# ltk-hall-main.net
KiCad netlist of a schematic drawn in Altium Designer
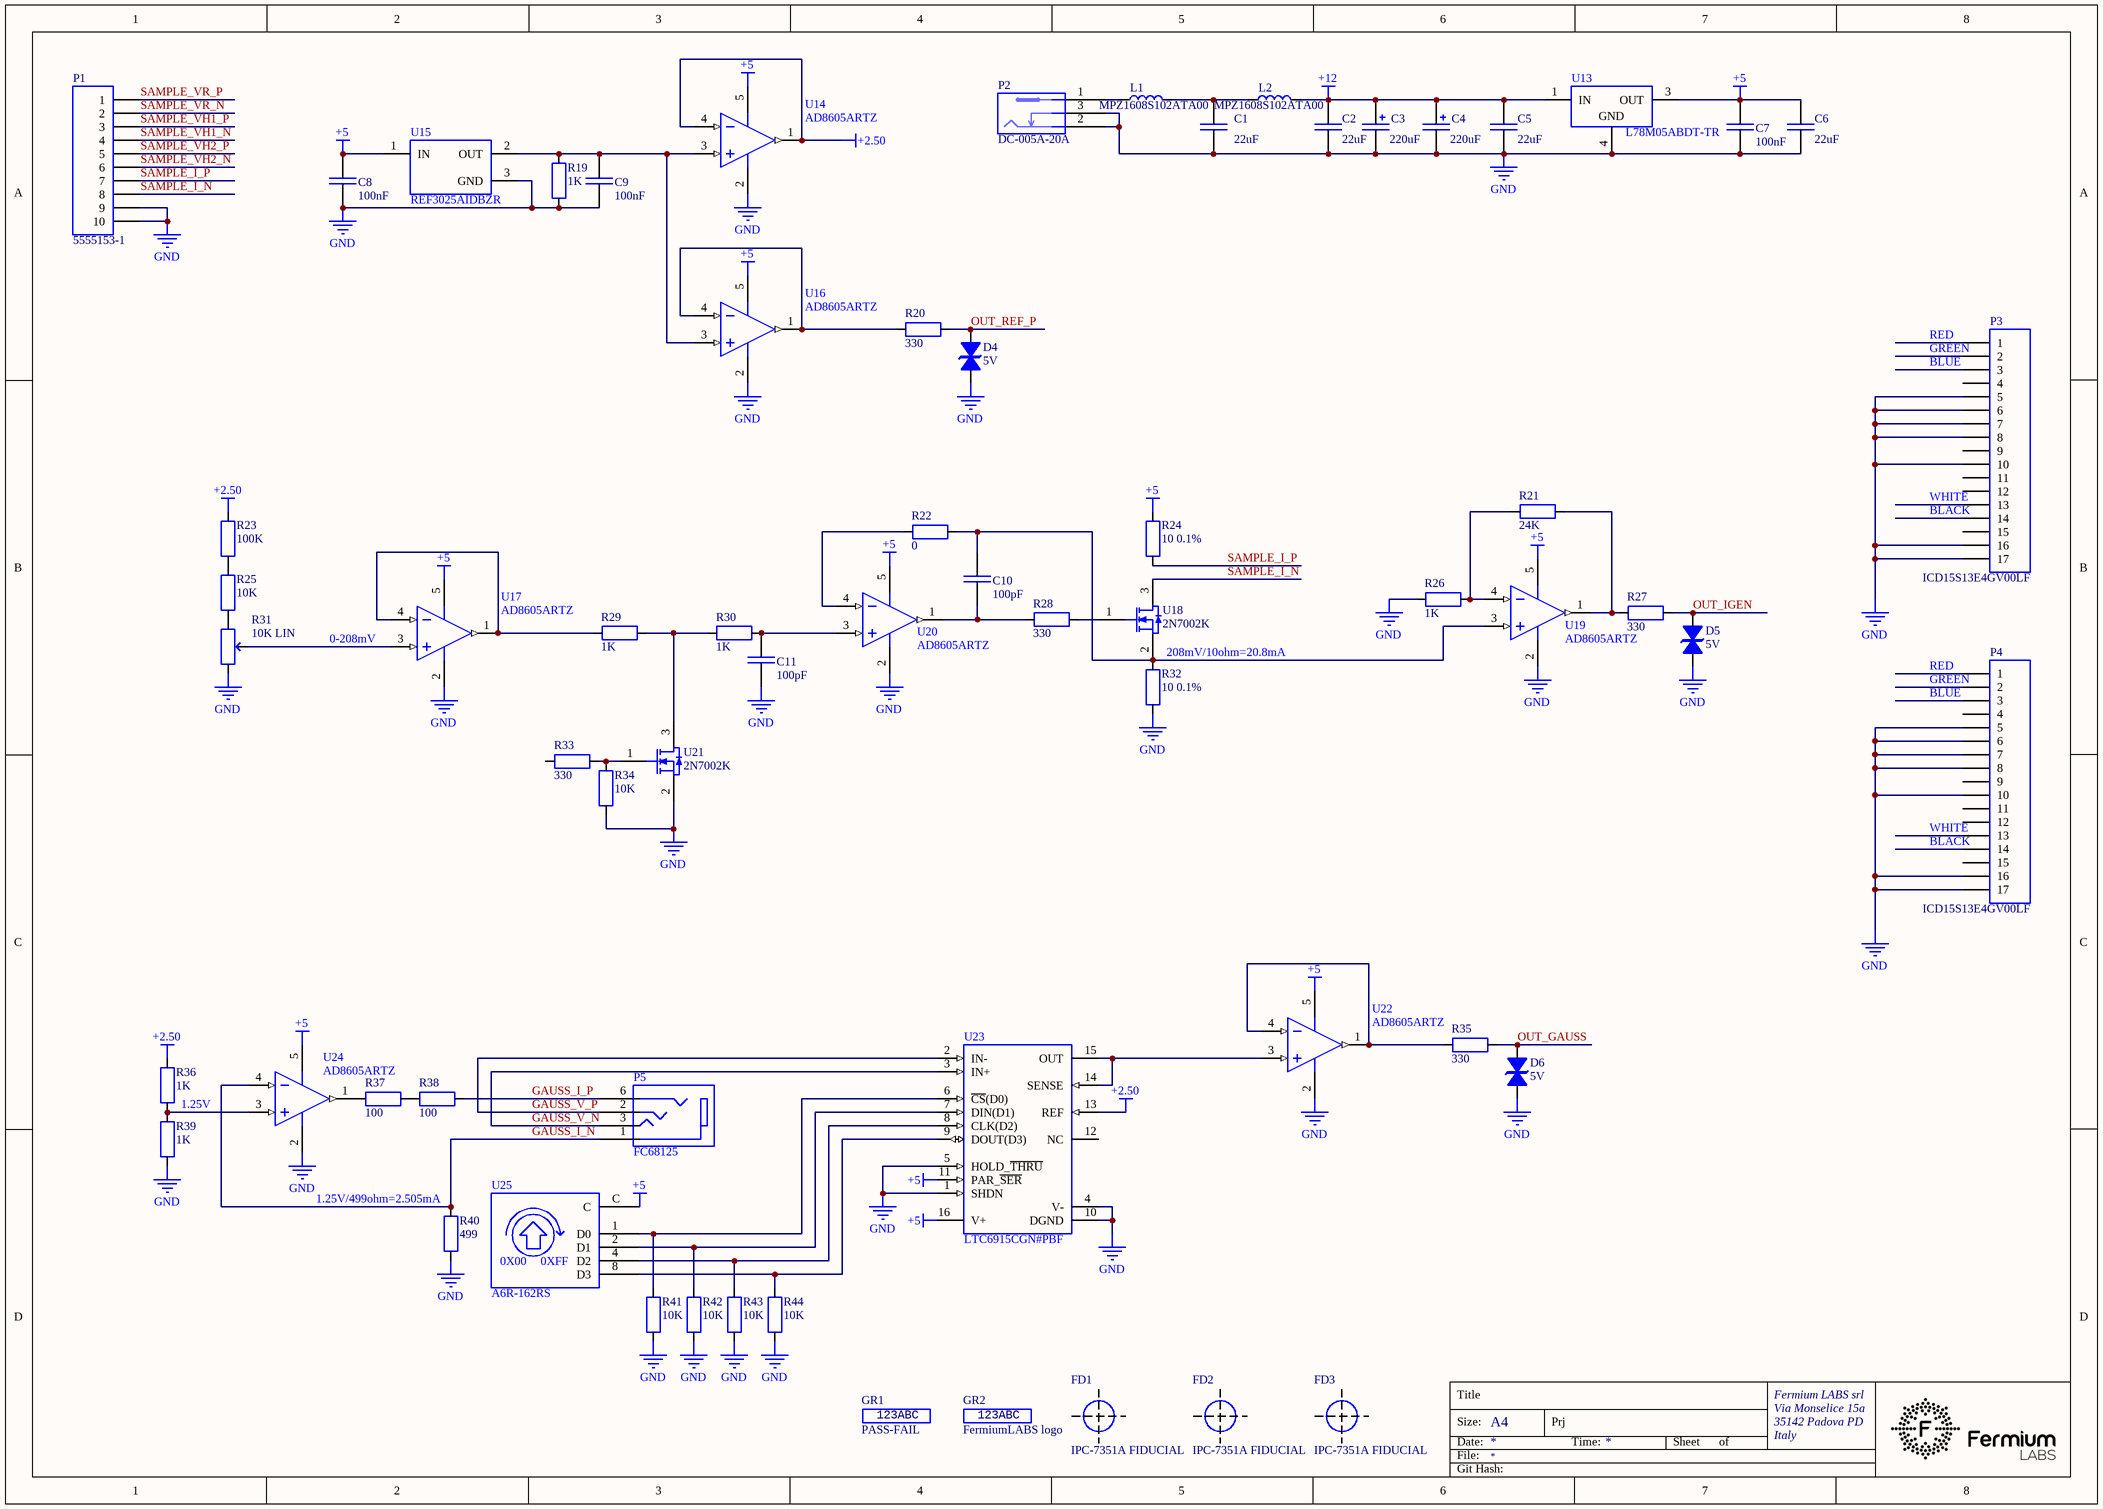
[diagram p0: ltk-hall-main.SchDoc]

(export (version "E")
  (design (tool "Eeschema 10.0.6"))
  (components
    (comp (ref "C1")
      (value "22uF")
      (footprint "CAP 0805_2012")
      (description "CAP SMD MLCC 22uF 25V 0805 X5R")
      (fields (field (name "PART NUMBER") "4e18e584-a077-4dfe-b9da-5e528e787323"))
      (libsource (lib "frmdblib") (part "GENERIC_C"))
    )
    (comp (ref "C2")
      (value "22uF")
      (footprint "CAP 0805_2012")
      (description "CAP SMD MLCC 22uF 25V 0805 X5R")
      (fields (field (name "PART NUMBER") "4e18e584-a077-4dfe-b9da-5e528e787323"))
      (libsource (lib "frmdblib") (part "GENERIC_C"))
    )
    (comp (ref "C3")
      (value "220uF")
      (footprint "3924B366-8672-45E9-B0BE-62DACC24E783")
      (description "CAP  THT ELEC 220uF 25V 20%")
      (fields (field (name "PART NUMBER") "1a28df19-6d3e-4a71-836c-f22920f8e8ab"))
      (libsource (lib "frmdblib") (part "GENERIC_C_ELEC"))
    )
    (comp (ref "C4")
      (value "220uF")
      (footprint "3924B366-8672-45E9-B0BE-62DACC24E783")
      (description "CAP  THT ELEC 220uF 25V 20%")
      (fields (field (name "PART NUMBER") "1a28df19-6d3e-4a71-836c-f22920f8e8ab"))
      (libsource (lib "frmdblib") (part "GENERIC_C_ELEC"))
    )
    (comp (ref "C5")
      (value "22uF")
      (footprint "CAP 0805_2012")
      (description "CAP SMD MLCC 22uF 25V 0805 X5R")
      (fields (field (name "PART NUMBER") "4e18e584-a077-4dfe-b9da-5e528e787323"))
      (libsource (lib "frmdblib") (part "GENERIC_C"))
    )
    (comp (ref "C6")
      (value "22uF")
      (footprint "CAP 0805_2012")
      (description "CAP SMD MLCC 22uF 25V 0805 X5R")
      (fields (field (name "PART NUMBER") "4e18e584-a077-4dfe-b9da-5e528e787323"))
      (libsource (lib "frmdblib") (part "GENERIC_C"))
    )
    (comp (ref "C7")
      (value "100nF")
      (footprint "CAP 0603_1608")
      (description "CAP SMD MLCC 100nF 25V 0603 X7R")
      (fields (field (name "PART NUMBER") "02841f84-ac15-41b5-9e17-915f8f067828"))
      (libsource (lib "frmdblib") (part "GENERIC_C"))
    )
    (comp (ref "C8")
      (value "100nF")
      (footprint "CAP 0603_1608")
      (description "CAP SMD MLCC 100nF 25V 0603 X7R")
      (fields (field (name "PART NUMBER") "02841f84-ac15-41b5-9e17-915f8f067828"))
      (libsource (lib "frmdblib") (part "GENERIC_C"))
    )
    (comp (ref "C9")
      (value "100nF")
      (footprint "CAP 0603_1608")
      (description "CAP SMD MLCC 100nF 25V 0603 X7R")
      (fields (field (name "PART NUMBER") "02841f84-ac15-41b5-9e17-915f8f067828"))
      (libsource (lib "frmdblib") (part "GENERIC_C"))
    )
    (comp (ref "C10")
      (value "100pF")
      (footprint "CAP 0603_1608")
      (description "CAP SMD MLCC 100pF 100V 0603 C0G/NP0")
      (fields (field (name "PART NUMBER") "ccf679fd-1b09-4431-be81-04c3ce295510"))
      (libsource (lib "frmdblib") (part "GENERIC_C"))
    )
    (comp (ref "C11")
      (value "100pF")
      (footprint "CAP 0603_1608")
      (description "CAP SMD MLCC 100pF 100V 0603 C0G/NP0")
      (fields (field (name "PART NUMBER") "ccf679fd-1b09-4431-be81-04c3ce295510"))
      (libsource (lib "frmdblib") (part "GENERIC_C"))
    )
    (comp (ref "D4")
      (value "5V")
      (footprint "SOD523F")
      (description "DIODE SMD TVS 5V BIDIRECTIONAL SOD-523")
      (fields (field (name "PART NUMBER") "daa58212-38e2-4326-a156-8e48058c46f1"))
      (libsource (lib "frmdblib") (part "GENERIC_D_TVS_BI"))
    )
    (comp (ref "D5")
      (value "5V")
      (footprint "SOD523F")
      (description "DIODE SMD TVS 5V BIDIRECTIONAL SOD-523")
      (fields (field (name "PART NUMBER") "daa58212-38e2-4326-a156-8e48058c46f1"))
      (libsource (lib "frmdblib") (part "GENERIC_D_TVS_BI"))
    )
    (comp (ref "D6")
      (value "5V")
      (footprint "SOD523F")
      (description "DIODE SMD TVS 5V BIDIRECTIONAL SOD-523")
      (fields (field (name "PART NUMBER") "daa58212-38e2-4326-a156-8e48058c46f1"))
      (libsource (lib "frmdblib") (part "GENERIC_D_TVS_BI"))
    )
    (comp (ref "FD1")
      (value "IPC-7351A FIDUCIAL")
      (footprint "FIDUCIAL-IPC-7351A")
      (description "GRAPHICS FIDUCIAL IPC-7351A")
      (fields (field (name "PART NUMBER") "19da4612-eb95-43bb-9984-553a52b2a224"))
      (libsource (lib "frmdblib") (part "GENERIC_FIDUCIAL"))
    )
    (comp (ref "FD2")
      (value "IPC-7351A FIDUCIAL")
      (footprint "FIDUCIAL-IPC-7351A")
      (description "GRAPHICS FIDUCIAL IPC-7351A")
      (fields (field (name "PART NUMBER") "19da4612-eb95-43bb-9984-553a52b2a224"))
      (libsource (lib "frmdblib") (part "GENERIC_FIDUCIAL"))
    )
    (comp (ref "FD3")
      (value "IPC-7351A FIDUCIAL")
      (footprint "FIDUCIAL-IPC-7351A")
      (description "GRAPHICS FIDUCIAL IPC-7351A")
      (fields (field (name "PART NUMBER") "19da4612-eb95-43bb-9984-553a52b2a224"))
      (libsource (lib "frmdblib") (part "GENERIC_FIDUCIAL"))
    )
    (comp (ref "GR1")
      (value "PASS-FAIL")
      (footprint "0B1556B7-A534-4801-B57D-01EFA34B1205")
      (description "GRAPHICS PASS-FAIL MARK")
      (fields (field (name "PART NUMBER") "d1abe19f-3fed-4f20-b2ed-afc0ffbc6628"))
      (libsource (lib "frmdblib") (part "GENERIC_GRAPHIC"))
    )
    (comp (ref "GR2")
      (value "FermiumLABS logo")
      (footprint "5394DE47-A0E8-4329-8464-7791B7C19310")
      (description "GRAPHICS LOGO FERMIUM LABS SRL")
      (fields (field (name "PART NUMBER") "50f8ea88-0034-49fe-a263-d8e97bc35e2f"))
      (libsource (lib "frmdblib") (part "GENERIC_GRAPHIC"))
    )
    (comp (ref "L1")
      (value "MPZ1608S102ATA00")
      (footprint "FER 0603_1608")
      (description "FER SMD CHIP 0603 800mA 1K@100MHz 300mOhm")
      (fields (field (name "PART NUMBER") "a4b2e015-bf25-47b8-954c-a5b040744a3a"))
      (libsource (lib "frmdblib") (part "GENERIC_L"))
    )
    (comp (ref "L2")
      (value "MPZ1608S102ATA00")
      (footprint "FER 0603_1608")
      (description "FER SMD CHIP 0603 800mA 1K@100MHz 300mOhm")
      (fields (field (name "PART NUMBER") "a4b2e015-bf25-47b8-954c-a5b040744a3a"))
      (libsource (lib "frmdblib") (part "GENERIC_L"))
    )
    (comp (ref "P1")
      (value "5555153-1")
      (footprint "03FA2727-72E9-446E-856D-3DD573B1EBDD")
      (description "CONN RJ45 SHIELDED")
      (fields (field (name "PART NUMBER") "f401b84a-9695-45b1-951e-00bef0039069"))
      (libsource (lib "frmdblib") (part "Header 10"))
    )
    (comp (ref "P2")
      (value "DC-005A-20A")
      (footprint "F0972D8A-C5C0-4A84-836D-A9666EE65C2D")
      (description "CONN THT DC JACK 0.5A 30VDC 5Kcycles")
      (fields (field (name "PART NUMBER") "b53db51a-1725-412b-9039-fa7a45c7c438"))
      (libsource (lib "frmdblib") (part "34A1CD0B-E262-46EF-B9F1-39CB809C308F"))
    )
    (comp (ref "P3")
      (value "ICD15S13E4GV00LF")
      (footprint "66D8AC91-DC10-42D3-BF25-693004815827")
      (description "CONN D-SUB HD 15POLES BLACK THT")
      (fields (field (name "PART NUMBER") "af155709-b835-40ac-b9b5-4a44b0fd2777"))
      (libsource (lib "frmdblib") (part "Header 17"))
    )
    (comp (ref "P4")
      (value "ICD15S13E4GV00LF")
      (footprint "66D8AC91-DC10-42D3-BF25-693004815827")
      (description "CONN D-SUB HD 15POLES BLACK THT")
      (fields (field (name "PART NUMBER") "af155709-b835-40ac-b9b5-4a44b0fd2777"))
      (libsource (lib "frmdblib") (part "Header 17"))
    )
    (comp (ref "P5")
      (value "FC68125")
      (footprint "977BFFC7-4CFC-4119-A8B4-AB88E5A1DB2B")
      (description "CONN JACK 3.5MM 4POLE THT")
      (fields (field (name "PART NUMBER") "3e3c57e9-f1b8-4c12-8bb1-97da9eb9c220"))
      (libsource (lib "frmdblib") (part "A6099F20-3616-40CA-8CCB-374681413BA7"))
    )
    (comp (ref "R19")
      (value "1K")
      (footprint "RES 0603_1608")
      (description "RES SMD 1K OHM 1% 1/10W 0603")
      (fields (field (name "PART NUMBER") "a678220f-9e9d-4863-a833-9993504f723c"))
      (libsource (lib "frmdblib") (part "GENERIC_R"))
    )
    (comp (ref "R20")
      (value "330")
      (description "RES SMD 330 OHM 1% 1/10W 0603")
      (fields (field (name "PART NUMBER") "e8555d7b-eeda-4727-b2e1-550cdc03d819"))
      (libsource (lib "frmdblib") (part "GENERIC_R"))
    )
    (comp (ref "R21")
      (value "24K")
      (description "RES SMD 24K OHM 1% 1/10W 0603")
      (fields (field (name "PART NUMBER") "89bb9559-07ab-4a9e-ba67-95cb66f30425"))
      (libsource (lib "frmdblib") (part "GENERIC_R"))
    )
    (comp (ref "R22")
      (value "0")
      (footprint "RES 0603_1608")
      (description "RES SMD 0 OHM 5% 1/10W 0603")
      (fields (field (name "PART NUMBER") "6ae227f9-847f-4766-8522-e11a83531204"))
      (libsource (lib "frmdblib") (part "GENERIC_R"))
    )
    (comp (ref "R23")
      (value "100K")
      (description "RES SMD 100K OHM 1% 1/16W 0402")
      (fields (field (name "PART NUMBER") "a6f23dcb-1502-42e9-827e-4bdfa60be22f"))
      (libsource (lib "frmdblib") (part "GENERIC_R"))
    )
    (comp (ref "R24")
      (value "10 0.1%")
      (footprint "RES 0603_1608")
      (description "RES SMD 10 OHM 0.1% 1/16W 25ppm  0603")
      (fields (field (name "PART NUMBER") "f0166db1-b7e4-4c18-9511-2907615c1c51"))
      (libsource (lib "frmdblib") (part "GENERIC_R"))
    )
    (comp (ref "R25")
      (value "10K")
      (footprint "RES 0603_1608")
      (description "RES SMD 10K OHM 1% 1/10W 0603")
      (fields (field (name "PART NUMBER") "93242766-ba1d-462d-b58f-ce1dfc4129c8"))
      (libsource (lib "frmdblib") (part "GENERIC_R"))
    )
    (comp (ref "R26")
      (value "1K")
      (footprint "RES 0603_1608")
      (description "RES SMD 1K OHM 1% 1/10W 0603")
      (fields (field (name "PART NUMBER") "a678220f-9e9d-4863-a833-9993504f723c"))
      (libsource (lib "frmdblib") (part "GENERIC_R"))
    )
    (comp (ref "R27")
      (value "330")
      (description "RES SMD 330 OHM 1% 1/10W 0603")
      (fields (field (name "PART NUMBER") "e8555d7b-eeda-4727-b2e1-550cdc03d819"))
      (libsource (lib "frmdblib") (part "GENERIC_R"))
    )
    (comp (ref "R28")
      (value "330")
      (description "RES SMD 330 OHM 1% 1/10W 0603")
      (fields (field (name "PART NUMBER") "e8555d7b-eeda-4727-b2e1-550cdc03d819"))
      (libsource (lib "frmdblib") (part "GENERIC_R"))
    )
    (comp (ref "R29")
      (value "1K")
      (footprint "RES 0603_1608")
      (description "RES SMD 1K OHM 1% 1/10W 0603")
      (fields (field (name "PART NUMBER") "a678220f-9e9d-4863-a833-9993504f723c"))
      (libsource (lib "frmdblib") (part "GENERIC_R"))
    )
    (comp (ref "R30")
      (value "1K")
      (footprint "RES 0603_1608")
      (description "RES SMD 1K OHM 1% 1/10W 0603")
      (fields (field (name "PART NUMBER") "a678220f-9e9d-4863-a833-9993504f723c"))
      (libsource (lib "frmdblib") (part "GENERIC_R"))
    )
    (comp (ref "R31")
      (value "10K LIN")
      (footprint "2EF88547-EDEF-4A49-A522-C215618D4BC7")
      (description "POT 10K 20% SHAFT 6mmx7.4mm LIN")
      (fields (field (name "PART NUMBER") "3df905ea-1e80-4add-859d-a36edd7f106c"))
      (libsource (lib "frmdblib") (part "GENERIC_R_VAR"))
    )
    (comp (ref "R32")
      (value "10 0.1%")
      (footprint "RES 0603_1608")
      (description "RES SMD 10 OHM 0.1% 1/16W 25ppm  0603")
      (fields (field (name "PART NUMBER") "f0166db1-b7e4-4c18-9511-2907615c1c51"))
      (libsource (lib "frmdblib") (part "GENERIC_R"))
    )
    (comp (ref "R33")
      (value "330")
      (description "RES SMD 330 OHM 1% 1/10W 0603")
      (fields (field (name "PART NUMBER") "e8555d7b-eeda-4727-b2e1-550cdc03d819"))
      (libsource (lib "frmdblib") (part "GENERIC_R"))
    )
    (comp (ref "R34")
      (value "10K")
      (footprint "RES 0603_1608")
      (description "RES SMD 10K OHM 1% 1/10W 0603")
      (fields (field (name "PART NUMBER") "93242766-ba1d-462d-b58f-ce1dfc4129c8"))
      (libsource (lib "frmdblib") (part "GENERIC_R"))
    )
    (comp (ref "R35")
      (value "330")
      (description "RES SMD 330 OHM 1% 1/10W 0603")
      (fields (field (name "PART NUMBER") "e8555d7b-eeda-4727-b2e1-550cdc03d819"))
      (libsource (lib "frmdblib") (part "GENERIC_R"))
    )
    (comp (ref "R36")
      (value "1K")
      (footprint "RES 0603_1608")
      (description "RES SMD 1K OHM 1% 1/10W 0603")
      (fields (field (name "PART NUMBER") "a678220f-9e9d-4863-a833-9993504f723c"))
      (libsource (lib "frmdblib") (part "GENERIC_R"))
    )
    (comp (ref "R37")
      (value "100")
      (description "RES SMD 100 OHM 1% 1/10W 0603")
      (fields (field (name "PART NUMBER") "0a6c4b74-f837-4563-b154-6e196d753525"))
      (libsource (lib "frmdblib") (part "GENERIC_R"))
    )
    (comp (ref "R38")
      (value "100")
      (description "RES SMD 100 OHM 1% 1/10W 0603")
      (fields (field (name "PART NUMBER") "0a6c4b74-f837-4563-b154-6e196d753525"))
      (libsource (lib "frmdblib") (part "GENERIC_R"))
    )
    (comp (ref "R39")
      (value "1K")
      (footprint "RES 0603_1608")
      (description "RES SMD 1K OHM 1% 1/10W 0603")
      (fields (field (name "PART NUMBER") "a678220f-9e9d-4863-a833-9993504f723c"))
      (libsource (lib "frmdblib") (part "GENERIC_R"))
    )
    (comp (ref "R40")
      (value "499")
      (description "RES SMD 499 OHM 1% 1/10W 0603")
      (fields (field (name "PART NUMBER") "3a10051a-dd65-4121-b0b9-1b40351a1843"))
      (libsource (lib "frmdblib") (part "GENERIC_R"))
    )
    (comp (ref "R41")
      (value "10K")
      (footprint "RES 0603_1608")
      (description "RES SMD 10K OHM 1% 1/10W 0603")
      (fields (field (name "PART NUMBER") "93242766-ba1d-462d-b58f-ce1dfc4129c8"))
      (libsource (lib "frmdblib") (part "GENERIC_R"))
    )
    (comp (ref "R42")
      (value "10K")
      (footprint "RES 0603_1608")
      (description "RES SMD 10K OHM 1% 1/10W 0603")
      (fields (field (name "PART NUMBER") "93242766-ba1d-462d-b58f-ce1dfc4129c8"))
      (libsource (lib "frmdblib") (part "GENERIC_R"))
    )
    (comp (ref "R43")
      (value "10K")
      (footprint "RES 0603_1608")
      (description "RES SMD 10K OHM 1% 1/10W 0603")
      (fields (field (name "PART NUMBER") "93242766-ba1d-462d-b58f-ce1dfc4129c8"))
      (libsource (lib "frmdblib") (part "GENERIC_R"))
    )
    (comp (ref "R44")
      (value "10K")
      (footprint "RES 0603_1608")
      (description "RES SMD 10K OHM 1% 1/10W 0603")
      (fields (field (name "PART NUMBER") "93242766-ba1d-462d-b58f-ce1dfc4129c8"))
      (libsource (lib "frmdblib") (part "GENERIC_R"))
    )
    (comp (ref "U13")
      (value "L78M05ABDT-TR")
      (footprint "4BDA507D-BB70-4009-B963-85AD90086B51")
      (description "IC SMD LINEAR VOLTAGE REGULATOR 5V 500mA DPAK/TO-252")
      (fields (field (name "PART NUMBER") "446536aa-1bdd-4764-8cae-49f4e0c126ff"))
      (libsource (lib "frmdblib") (part "568C7F7F-B71D-457E-B5FB-AE9D42DA8928"))
    )
    (comp (ref "U14")
      (value "AD8605ARTZ")
      (footprint "A3DDA0BC-073E-4B18-9613-F713A7EC1E27")
      (description "IC OPAMP 65uV 1pA RRIO 5V 80mA SOT-23-5")
      (fields (field (name "PART NUMBER") "5610e9ea-bca8-49b2-8e5f-11409231f6a4"))
      (libsource (lib "frmdblib") (part "8096D751-9DCE-401B-B65E-AAEE0733EA70"))
    )
    (comp (ref "U15")
      (value "REF3025AIDBZR")
      (footprint "TI SOT-23-3 DBZ")
      (description "IC VOLTAGE REF SERIES 2.5V 75ppm 0.2% SOT-23")
      (fields (field (name "PART NUMBER") "0de0df07-6dfd-42d8-9fe7-171c27772811"))
      (libsource (lib "frmdblib") (part "7CD2CEE0-4EC4-4AB4-93FF-624CFED04EB7"))
    )
    (comp (ref "U16")
      (value "AD8605ARTZ")
      (footprint "A3DDA0BC-073E-4B18-9613-F713A7EC1E27")
      (description "IC OPAMP 65uV 1pA RRIO 5V 80mA SOT-23-5")
      (fields (field (name "PART NUMBER") "5610e9ea-bca8-49b2-8e5f-11409231f6a4"))
      (libsource (lib "frmdblib") (part "8096D751-9DCE-401B-B65E-AAEE0733EA70"))
    )
    (comp (ref "U17")
      (value "AD8605ARTZ")
      (footprint "A3DDA0BC-073E-4B18-9613-F713A7EC1E27")
      (description "IC OPAMP 65uV 1pA RRIO 5V 80mA SOT-23-5")
      (fields (field (name "PART NUMBER") "5610e9ea-bca8-49b2-8e5f-11409231f6a4"))
      (libsource (lib "frmdblib") (part "8096D751-9DCE-401B-B65E-AAEE0733EA70"))
    )
    (comp (ref "U18")
      (value "2N7002K")
      (footprint "ON SEMI SOT-23-3")
      (description "MOSFET N-CHANNEL LOGIC LEVEL 300mA 3ohm 60V ESD-PROT 2N7002K SOT-23")
      (fields (field (name "PART NUMBER") "3a318f0a-3b94-47d9-91d5-8fc0a2f410e8"))
      (libsource (lib "frmdblib") (part "GENERIC_N_MOSFET_GSD"))
    )
    (comp (ref "U19")
      (value "AD8605ARTZ")
      (footprint "A3DDA0BC-073E-4B18-9613-F713A7EC1E27")
      (description "IC OPAMP 65uV 1pA RRIO 5V 80mA SOT-23-5")
      (fields (field (name "PART NUMBER") "5610e9ea-bca8-49b2-8e5f-11409231f6a4"))
      (libsource (lib "frmdblib") (part "8096D751-9DCE-401B-B65E-AAEE0733EA70"))
    )
    (comp (ref "U20")
      (value "AD8605ARTZ")
      (footprint "A3DDA0BC-073E-4B18-9613-F713A7EC1E27")
      (description "IC OPAMP 65uV 1pA RRIO 5V 80mA SOT-23-5")
      (fields (field (name "PART NUMBER") "5610e9ea-bca8-49b2-8e5f-11409231f6a4"))
      (libsource (lib "frmdblib") (part "8096D751-9DCE-401B-B65E-AAEE0733EA70"))
    )
    (comp (ref "U21")
      (value "2N7002K")
      (footprint "ON SEMI SOT-23-3")
      (description "MOSFET N-CHANNEL LOGIC LEVEL 300mA 3ohm 60V ESD-PROT 2N7002K SOT-23")
      (fields (field (name "PART NUMBER") "3a318f0a-3b94-47d9-91d5-8fc0a2f410e8"))
      (libsource (lib "frmdblib") (part "GENERIC_N_MOSFET_GSD"))
    )
    (comp (ref "U22")
      (value "AD8605ARTZ")
      (footprint "A3DDA0BC-073E-4B18-9613-F713A7EC1E27")
      (description "IC OPAMP 65uV 1pA RRIO 5V 80mA SOT-23-5")
      (fields (field (name "PART NUMBER") "5610e9ea-bca8-49b2-8e5f-11409231f6a4"))
      (libsource (lib "frmdblib") (part "8096D751-9DCE-401B-B65E-AAEE0733EA70"))
    )
    (comp (ref "U23")
      (value "LTC6915CGN#PBF")
      (footprint "517EE8A2-9FD8-4174-996D-BDBF76CA3EEB")
      (description "IC PGA G0-4094 SPI-PARALLEL 5V RRIO SSOP-16")
      (fields (field (name "PART NUMBER") "59fe82cd-fd18-4813-9f52-e2e78a460aff"))
      (libsource (lib "frmdblib") (part "092C41BF-C4B2-4D13-B4E9-531E546592A0"))
    )
    (comp (ref "U24")
      (value "AD8605ARTZ")
      (footprint "A3DDA0BC-073E-4B18-9613-F713A7EC1E27")
      (description "IC OPAMP 65uV 1pA RRIO 5V 80mA SOT-23-5")
      (fields (field (name "PART NUMBER") "5610e9ea-bca8-49b2-8e5f-11409231f6a4"))
      (libsource (lib "frmdblib") (part "8096D751-9DCE-401B-B65E-AAEE0733EA70"))
    )
    (comp (ref "U25")
      (value "A6R-162RS")
      (footprint "2599C238-5645-4A8C-8BF9-C7515FACCFA0")
      (description "SWITCH ROTARY HEX/BCD 16 POSITIONS")
      (fields (field (name "PART NUMBER") "bbf157ad-cd7a-4e82-97e3-d6a037590888"))
      (libsource (lib "frmdblib") (part "EFC705A0-D700-486A-81AB-6EE045EE6C24"))
    )
  )
  (nets
    (net (code "1") (name "+2.50") (class "Default")
      (node (ref "R23") (pin "2") (pintype "passive"))
      (node (ref "R36") (pin "2") (pintype "passive"))
      (node (ref "U14") (pin "1") (pinfunction "OUT_1") (pintype "output"))
      (node (ref "U14") (pin "4") (pinfunction "-IN_4") (pintype "input"))
      (node (ref "U23") (pin "13") (pinfunction "REF_13") (pintype "input"))
    )
    (net (code "2") (name "+5") (class "Default")
      (node (ref "C6") (pin "1") (pintype "passive"))
      (node (ref "C7") (pin "1") (pintype "passive"))
      (node (ref "C8") (pin "1") (pintype "passive"))
      (node (ref "R24") (pin "2") (pintype "passive"))
      (node (ref "U13") (pin "3") (pinfunction "OUT_3") (pintype "power_in"))
      (node (ref "U14") (pin "5") (pinfunction "+V_5") (pintype "power_in"))
      (node (ref "U15") (pin "1") (pinfunction "IN_1") (pintype "power_in"))
      (node (ref "U16") (pin "5") (pinfunction "+V_5") (pintype "power_in"))
      (node (ref "U17") (pin "5") (pinfunction "+V_5") (pintype "power_in"))
      (node (ref "U19") (pin "5") (pinfunction "+V_5") (pintype "power_in"))
      (node (ref "U20") (pin "5") (pinfunction "+V_5") (pintype "power_in"))
      (node (ref "U22") (pin "5") (pinfunction "+V_5") (pintype "power_in"))
      (node (ref "U23") (pin "11") (pinfunction "PAR_~{SER}_11") (pintype "input"))
      (node (ref "U23") (pin "16") (pinfunction "V+_16") (pintype "power_in"))
      (node (ref "U24") (pin "5") (pinfunction "+V_5") (pintype "power_in"))
      (node (ref "U25") (pin "C") (pinfunction "C_C") (pintype "passive"))
    )
    (net (code "3") (name "+12") (class "Default")
      (node (ref "C2") (pin "1") (pintype "passive"))
      (node (ref "C3") (pin "1") (pintype "passive"))
      (node (ref "C4") (pin "1") (pintype "passive"))
      (node (ref "C5") (pin "1") (pintype "passive"))
      (node (ref "L2") (pin "2") (pintype "passive"))
      (node (ref "U13") (pin "1") (pinfunction "IN_1") (pintype "power_in"))
    )
    (net (code "4") (name "/GAUSS_I_N") (class "Default")
      (node (ref "P5") (pin "1") (pinfunction "1_1") (pintype "passive"))
      (node (ref "R40") (pin "2") (pintype "passive"))
      (node (ref "U24") (pin "4") (pinfunction "-IN_4") (pintype "input"))
    )
    (net (code "5") (name "/GAUSS_I_P") (class "Default")
      (node (ref "P5") (pin "6") (pinfunction "6_6") (pintype "passive"))
      (node (ref "R38") (pin "2") (pintype "passive"))
    )
    (net (code "6") (name "/GAUSS_V_N") (class "Default")
      (node (ref "P5") (pin "3") (pinfunction "3_3") (pintype "passive"))
      (node (ref "U23") (pin "3") (pinfunction "IN+_3") (pintype "input"))
    )
    (net (code "7") (name "/GAUSS_V_P") (class "Default")
      (node (ref "P5") (pin "2") (pinfunction "2_2") (pintype "passive"))
      (node (ref "U23") (pin "2") (pinfunction "IN-_2") (pintype "input"))
    )
    (net (code "8") (name "/OUT_GAUSS") (class "Default")
      (node (ref "D6") (pin "1") (pintype "passive"))
      (node (ref "R35") (pin "2") (pintype "passive"))
    )
    (net (code "9") (name "/OUT_IGEN") (class "Default")
      (node (ref "D5") (pin "1") (pintype "passive"))
      (node (ref "R27") (pin "2") (pintype "passive"))
    )
    (net (code "10") (name "/OUT_REF_P") (class "Default")
      (node (ref "D4") (pin "1") (pintype "passive"))
      (node (ref "R20") (pin "2") (pintype "passive"))
    )
    (net (code "11") (name "/SAMPLE_I_N") (class "Default")
      (node (ref "P1") (pin "8") (pinfunction "8_8") (pintype "passive"))
      (node (ref "U18") (pin "3") (pinfunction "D_3") (pintype "passive"))
    )
    (net (code "12") (name "/SAMPLE_I_P") (class "Default")
      (node (ref "P1") (pin "7") (pinfunction "7_7") (pintype "passive"))
      (node (ref "R24") (pin "1") (pintype "passive"))
    )
    (net (code "13") (name "/SAMPLE_VH1_N") (class "Default")
      (node (ref "P1") (pin "4") (pinfunction "4_4") (pintype "passive"))
    )
    (net (code "14") (name "/SAMPLE_VH1_P") (class "Default")
      (node (ref "P1") (pin "3") (pinfunction "3_3") (pintype "passive"))
    )
    (net (code "15") (name "/SAMPLE_VH2_N") (class "Default")
      (node (ref "P1") (pin "6") (pinfunction "6_6") (pintype "passive"))
    )
    (net (code "16") (name "/SAMPLE_VH2_P") (class "Default")
      (node (ref "P1") (pin "5") (pinfunction "5_5") (pintype "passive"))
    )
    (net (code "17") (name "/SAMPLE_VR_N") (class "Default")
      (node (ref "P1") (pin "2") (pinfunction "2_2") (pintype "passive"))
    )
    (net (code "18") (name "/SAMPLE_VR_P") (class "Default")
      (node (ref "P1") (pin "1") (pinfunction "1_1") (pintype "passive"))
    )
    (net (code "19") (name "GND") (class "Default")
      (node (ref "C1") (pin "2") (pintype "passive"))
      (node (ref "C11") (pin "2") (pintype "passive"))
      (node (ref "C2") (pin "2") (pintype "passive"))
      (node (ref "C3") (pin "2") (pintype "passive"))
      (node (ref "C4") (pin "2") (pintype "passive"))
      (node (ref "C5") (pin "2") (pintype "passive"))
      (node (ref "C6") (pin "2") (pintype "passive"))
      (node (ref "C7") (pin "2") (pintype "passive"))
      (node (ref "C8") (pin "2") (pintype "passive"))
      (node (ref "C9") (pin "2") (pintype "passive"))
      (node (ref "D4") (pin "2") (pintype "passive"))
      (node (ref "D5") (pin "2") (pintype "passive"))
      (node (ref "D6") (pin "2") (pintype "passive"))
      (node (ref "P1") (pin "10") (pinfunction "10_10") (pintype "passive"))
      (node (ref "P1") (pin "9") (pinfunction "9_9") (pintype "passive"))
      (node (ref "P2") (pin "2") (pinfunction "2_2") (pintype "passive"))
      (node (ref "P2") (pin "3") (pinfunction "3_3") (pintype "passive"))
      (node (ref "P3") (pin "10") (pinfunction "10_10") (pintype "passive"))
      (node (ref "P3") (pin "16") (pinfunction "16_16") (pintype "passive"))
      (node (ref "P3") (pin "17") (pinfunction "17_17") (pintype "passive"))
      (node (ref "P3") (pin "5") (pinfunction "5_5") (pintype "passive"))
      (node (ref "P3") (pin "6") (pinfunction "6_6") (pintype "passive"))
      (node (ref "P3") (pin "7") (pinfunction "7_7") (pintype "passive"))
      (node (ref "P3") (pin "8") (pinfunction "8_8") (pintype "passive"))
      (node (ref "P4") (pin "10") (pinfunction "10_10") (pintype "passive"))
      (node (ref "P4") (pin "16") (pinfunction "16_16") (pintype "passive"))
      (node (ref "P4") (pin "17") (pinfunction "17_17") (pintype "passive"))
      (node (ref "P4") (pin "5") (pinfunction "5_5") (pintype "passive"))
      (node (ref "P4") (pin "6") (pinfunction "6_6") (pintype "passive"))
      (node (ref "P4") (pin "7") (pinfunction "7_7") (pintype "passive"))
      (node (ref "P4") (pin "8") (pinfunction "8_8") (pintype "passive"))
      (node (ref "R19") (pin "1") (pintype "passive"))
      (node (ref "R26") (pin "1") (pintype "passive"))
      (node (ref "R31") (pin "3") (pintype "passive"))
      (node (ref "R32") (pin "1") (pintype "passive"))
      (node (ref "R34") (pin "1") (pintype "passive"))
      (node (ref "R39") (pin "1") (pintype "passive"))
      (node (ref "R40") (pin "1") (pintype "passive"))
      (node (ref "R41") (pin "1") (pintype "passive"))
      (node (ref "R42") (pin "1") (pintype "passive"))
      (node (ref "R43") (pin "1") (pintype "passive"))
      (node (ref "R44") (pin "1") (pintype "passive"))
      (node (ref "U13") (pin "4") (pinfunction "GND_4") (pintype "power_in"))
      (node (ref "U14") (pin "2") (pinfunction "-V_2") (pintype "power_in"))
      (node (ref "U15") (pin "3") (pinfunction "GND_3") (pintype "power_in"))
      (node (ref "U16") (pin "2") (pinfunction "-V_2") (pintype "power_in"))
      (node (ref "U17") (pin "2") (pinfunction "-V_2") (pintype "power_in"))
      (node (ref "U19") (pin "2") (pinfunction "-V_2") (pintype "power_in"))
      (node (ref "U20") (pin "2") (pinfunction "-V_2") (pintype "power_in"))
      (node (ref "U21") (pin "2") (pinfunction "S_2") (pintype "passive"))
      (node (ref "U22") (pin "2") (pinfunction "-V_2") (pintype "power_in"))
      (node (ref "U23") (pin "1") (pinfunction "SHDN_1") (pintype "input"))
      (node (ref "U23") (pin "10") (pinfunction "DGND_10") (pintype "power_in"))
      (node (ref "U23") (pin "4") (pinfunction "V-_4") (pintype "power_in"))
      (node (ref "U23") (pin "5") (pinfunction "HOLD_~{THRU}_5") (pintype "input"))
      (node (ref "U24") (pin "2") (pinfunction "-V_2") (pintype "power_in"))
    )
    (net (code "20") (name "Net-(C1-Pad1)") (class "Default")
      (node (ref "C1") (pin "1") (pintype "passive"))
      (node (ref "L1") (pin "2") (pintype "passive"))
      (node (ref "L2") (pin "1") (pintype "passive"))
    )
    (net (code "21") (name "Net-(L1-Pad1)") (class "Default")
      (node (ref "L1") (pin "1") (pintype "passive"))
      (node (ref "P2") (pin "1") (pinfunction "1_1") (pintype "passive"))
    )
    (net (code "22") (name "Net-(R23-Pad1)") (class "Default")
      (node (ref "R23") (pin "1") (pintype "passive"))
      (node (ref "R25") (pin "2") (pintype "passive"))
    )
    (net (code "23") (name "Net-(R25-Pad1)") (class "Default")
      (node (ref "R25") (pin "1") (pintype "passive"))
      (node (ref "R31") (pin "1") (pintype "passive"))
    )
    (net (code "24") (name "Net-(R37-Pad2)") (class "Default")
      (node (ref "R37") (pin "2") (pintype "passive"))
      (node (ref "R38") (pin "1") (pintype "passive"))
    )
    (net (code "25") (name "Net-(U14-+IN)") (class "Default")
      (node (ref "C9") (pin "1") (pintype "passive"))
      (node (ref "R19") (pin "2") (pintype "passive"))
      (node (ref "U14") (pin "3") (pinfunction "+IN_3") (pintype "input"))
      (node (ref "U15") (pin "2") (pinfunction "OUT_2") (pintype "power_in"))
      (node (ref "U16") (pin "3") (pinfunction "+IN_3") (pintype "input"))
    )
    (net (code "26") (name "Net-(U16--IN)") (class "Default")
      (node (ref "R20") (pin "1") (pintype "passive"))
      (node (ref "U16") (pin "1") (pinfunction "OUT_1") (pintype "output"))
      (node (ref "U16") (pin "4") (pinfunction "-IN_4") (pintype "input"))
    )
    (net (code "27") (name "Net-(U17-+IN)") (class "Default")
      (node (ref "R31") (pin "2") (pintype "passive"))
      (node (ref "U17") (pin "3") (pinfunction "+IN_3") (pintype "input"))
    )
    (net (code "28") (name "Net-(U17--IN)") (class "Default")
      (node (ref "R29") (pin "1") (pintype "passive"))
      (node (ref "U17") (pin "1") (pinfunction "OUT_1") (pintype "output"))
      (node (ref "U17") (pin "4") (pinfunction "-IN_4") (pintype "input"))
    )
    (net (code "29") (name "Net-(U18-G)") (class "Default")
      (node (ref "R28") (pin "2") (pintype "passive"))
      (node (ref "U18") (pin "1") (pinfunction "G_1") (pintype "passive"))
    )
    (net (code "30") (name "Net-(U18-S)") (class "Default")
      (node (ref "C10") (pin "1") (pintype "passive"))
      (node (ref "R22") (pin "2") (pintype "passive"))
      (node (ref "R32") (pin "2") (pintype "passive"))
      (node (ref "U18") (pin "2") (pinfunction "S_2") (pintype "passive"))
      (node (ref "U19") (pin "3") (pinfunction "+IN_3") (pintype "input"))
    )
    (net (code "31") (name "Net-(U19--IN)") (class "Default")
      (node (ref "R21") (pin "1") (pintype "passive"))
      (node (ref "R26") (pin "2") (pintype "passive"))
      (node (ref "U19") (pin "4") (pinfunction "-IN_4") (pintype "input"))
    )
    (net (code "32") (name "Net-(U19-OUT)") (class "Default")
      (node (ref "R21") (pin "2") (pintype "passive"))
      (node (ref "R27") (pin "1") (pintype "passive"))
      (node (ref "U19") (pin "1") (pinfunction "OUT_1") (pintype "output"))
    )
    (net (code "33") (name "Net-(U20-+IN)") (class "Default")
      (node (ref "C11") (pin "1") (pintype "passive"))
      (node (ref "R30") (pin "2") (pintype "passive"))
      (node (ref "U20") (pin "3") (pinfunction "+IN_3") (pintype "input"))
    )
    (net (code "34") (name "Net-(U20--IN)") (class "Default")
      (node (ref "R22") (pin "1") (pintype "passive"))
      (node (ref "U20") (pin "4") (pinfunction "-IN_4") (pintype "input"))
    )
    (net (code "35") (name "Net-(U20-OUT)") (class "Default")
      (node (ref "C10") (pin "2") (pintype "passive"))
      (node (ref "R28") (pin "1") (pintype "passive"))
      (node (ref "U20") (pin "1") (pinfunction "OUT_1") (pintype "output"))
    )
    (net (code "36") (name "Net-(U21-D)") (class "Default")
      (node (ref "R29") (pin "2") (pintype "passive"))
      (node (ref "R30") (pin "1") (pintype "passive"))
      (node (ref "U21") (pin "3") (pinfunction "D_3") (pintype "passive"))
    )
    (net (code "37") (name "Net-(U21-G)") (class "Default")
      (node (ref "R33") (pin "2") (pintype "passive"))
      (node (ref "R34") (pin "2") (pintype "passive"))
      (node (ref "U21") (pin "1") (pinfunction "G_1") (pintype "passive"))
    )
    (net (code "38") (name "Net-(U22-+IN)") (class "Default")
      (node (ref "U22") (pin "3") (pinfunction "+IN_3") (pintype "input"))
      (node (ref "U23") (pin "14") (pinfunction "SENSE_14") (pintype "input"))
      (node (ref "U23") (pin "15") (pinfunction "OUT_15") (pintype "tri_state"))
    )
    (net (code "39") (name "Net-(U22--IN)") (class "Default")
      (node (ref "R35") (pin "1") (pintype "passive"))
      (node (ref "U22") (pin "1") (pinfunction "OUT_1") (pintype "output"))
      (node (ref "U22") (pin "4") (pinfunction "-IN_4") (pintype "input"))
    )
    (net (code "40") (name "Net-(U23-CLK(D2))") (class "Default")
      (node (ref "R43") (pin "2") (pintype "passive"))
      (node (ref "U23") (pin "8") (pinfunction "CLK(D2)_8") (pintype "input"))
      (node (ref "U25") (pin "4") (pinfunction "D2_4") (pintype "passive"))
    )
    (net (code "41") (name "Net-(U23-DIN(D1))") (class "Default")
      (node (ref "R42") (pin "2") (pintype "passive"))
      (node (ref "U23") (pin "7") (pinfunction "DIN(D1)_7") (pintype "input"))
      (node (ref "U25") (pin "2") (pinfunction "D1_2") (pintype "passive"))
    )
    (net (code "42") (name "Net-(U23-DOUT(D3))") (class "Default")
      (node (ref "R44") (pin "2") (pintype "passive"))
      (node (ref "U23") (pin "9") (pinfunction "DOUT(D3)_9") (pintype "bidirectional"))
      (node (ref "U25") (pin "8") (pinfunction "D3_8") (pintype "passive"))
    )
    (net (code "43") (name "Net-(U23-~{CS}(D0))") (class "Default")
      (node (ref "R41") (pin "2") (pintype "passive"))
      (node (ref "U23") (pin "6") (pinfunction "~{CS}(D0)_6") (pintype "input"))
      (node (ref "U25") (pin "1") (pinfunction "D0_1") (pintype "passive"))
    )
    (net (code "44") (name "Net-(U24-+IN)") (class "Default")
      (node (ref "R36") (pin "1") (pintype "passive"))
      (node (ref "R39") (pin "2") (pintype "passive"))
      (node (ref "U24") (pin "3") (pinfunction "+IN_3") (pintype "input"))
    )
    (net (code "45") (name "Net-(U24-OUT)") (class "Default")
      (node (ref "R37") (pin "1") (pintype "passive"))
      (node (ref "U24") (pin "1") (pinfunction "OUT_1") (pintype "output"))
    )
    (net (code "46") (name "unconnected-(P3-Pad1)") (class "Default")
      (node (ref "P3") (pin "1") (pinfunction "1_1") (pintype "passive"))
    )
    (net (code "47") (name "unconnected-(P3-Pad2)") (class "Default")
      (node (ref "P3") (pin "2") (pinfunction "2_2") (pintype "passive"))
    )
    (net (code "48") (name "unconnected-(P3-Pad3)") (class "Default")
      (node (ref "P3") (pin "3") (pinfunction "3_3") (pintype "passive"))
    )
    (net (code "49") (name "unconnected-(P3-Pad4)") (class "Default")
      (node (ref "P3") (pin "4") (pinfunction "4_4") (pintype "passive"))
    )
    (net (code "50") (name "unconnected-(P3-Pad9)") (class "Default")
      (node (ref "P3") (pin "9") (pinfunction "9_9") (pintype "passive"))
    )
    (net (code "51") (name "unconnected-(P3-Pad11)") (class "Default")
      (node (ref "P3") (pin "11") (pinfunction "11_11") (pintype "passive"))
    )
    (net (code "52") (name "unconnected-(P3-Pad12)") (class "Default")
      (node (ref "P3") (pin "12") (pinfunction "12_12") (pintype "passive"))
    )
    (net (code "53") (name "unconnected-(P3-Pad13)") (class "Default")
      (node (ref "P3") (pin "13") (pinfunction "13_13") (pintype "passive"))
    )
    (net (code "54") (name "unconnected-(P3-Pad14)") (class "Default")
      (node (ref "P3") (pin "14") (pinfunction "14_14") (pintype "passive"))
    )
    (net (code "55") (name "unconnected-(P3-Pad15)") (class "Default")
      (node (ref "P3") (pin "15") (pinfunction "15_15") (pintype "passive"))
    )
    (net (code "56") (name "unconnected-(P4-Pad1)") (class "Default")
      (node (ref "P4") (pin "1") (pinfunction "1_1") (pintype "passive"))
    )
    (net (code "57") (name "unconnected-(P4-Pad2)") (class "Default")
      (node (ref "P4") (pin "2") (pinfunction "2_2") (pintype "passive"))
    )
    (net (code "58") (name "unconnected-(P4-Pad3)") (class "Default")
      (node (ref "P4") (pin "3") (pinfunction "3_3") (pintype "passive"))
    )
    (net (code "59") (name "unconnected-(P4-Pad4)") (class "Default")
      (node (ref "P4") (pin "4") (pinfunction "4_4") (pintype "passive"))
    )
    (net (code "60") (name "unconnected-(P4-Pad9)") (class "Default")
      (node (ref "P4") (pin "9") (pinfunction "9_9") (pintype "passive"))
    )
    (net (code "61") (name "unconnected-(P4-Pad11)") (class "Default")
      (node (ref "P4") (pin "11") (pinfunction "11_11") (pintype "passive"))
    )
    (net (code "62") (name "unconnected-(P4-Pad12)") (class "Default")
      (node (ref "P4") (pin "12") (pinfunction "12_12") (pintype "passive"))
    )
    (net (code "63") (name "unconnected-(P4-Pad13)") (class "Default")
      (node (ref "P4") (pin "13") (pinfunction "13_13") (pintype "passive"))
    )
    (net (code "64") (name "unconnected-(P4-Pad14)") (class "Default")
      (node (ref "P4") (pin "14") (pinfunction "14_14") (pintype "passive"))
    )
    (net (code "65") (name "unconnected-(P4-Pad15)") (class "Default")
      (node (ref "P4") (pin "15") (pinfunction "15_15") (pintype "passive"))
    )
    (net (code "66") (name "unconnected-(R33-Pad1)") (class "Default")
      (node (ref "R33") (pin "1") (pintype "passive"))
    )
    (net (code "67") (name "unconnected-(U23-NC-Pad12)") (class "Default")
      (node (ref "U23") (pin "12") (pinfunction "NC_12") (pintype "passive"))
    )
  )
)
